# diskohedron4w_revf.net
KiCad netlist of a schematic drawn in EAGLE
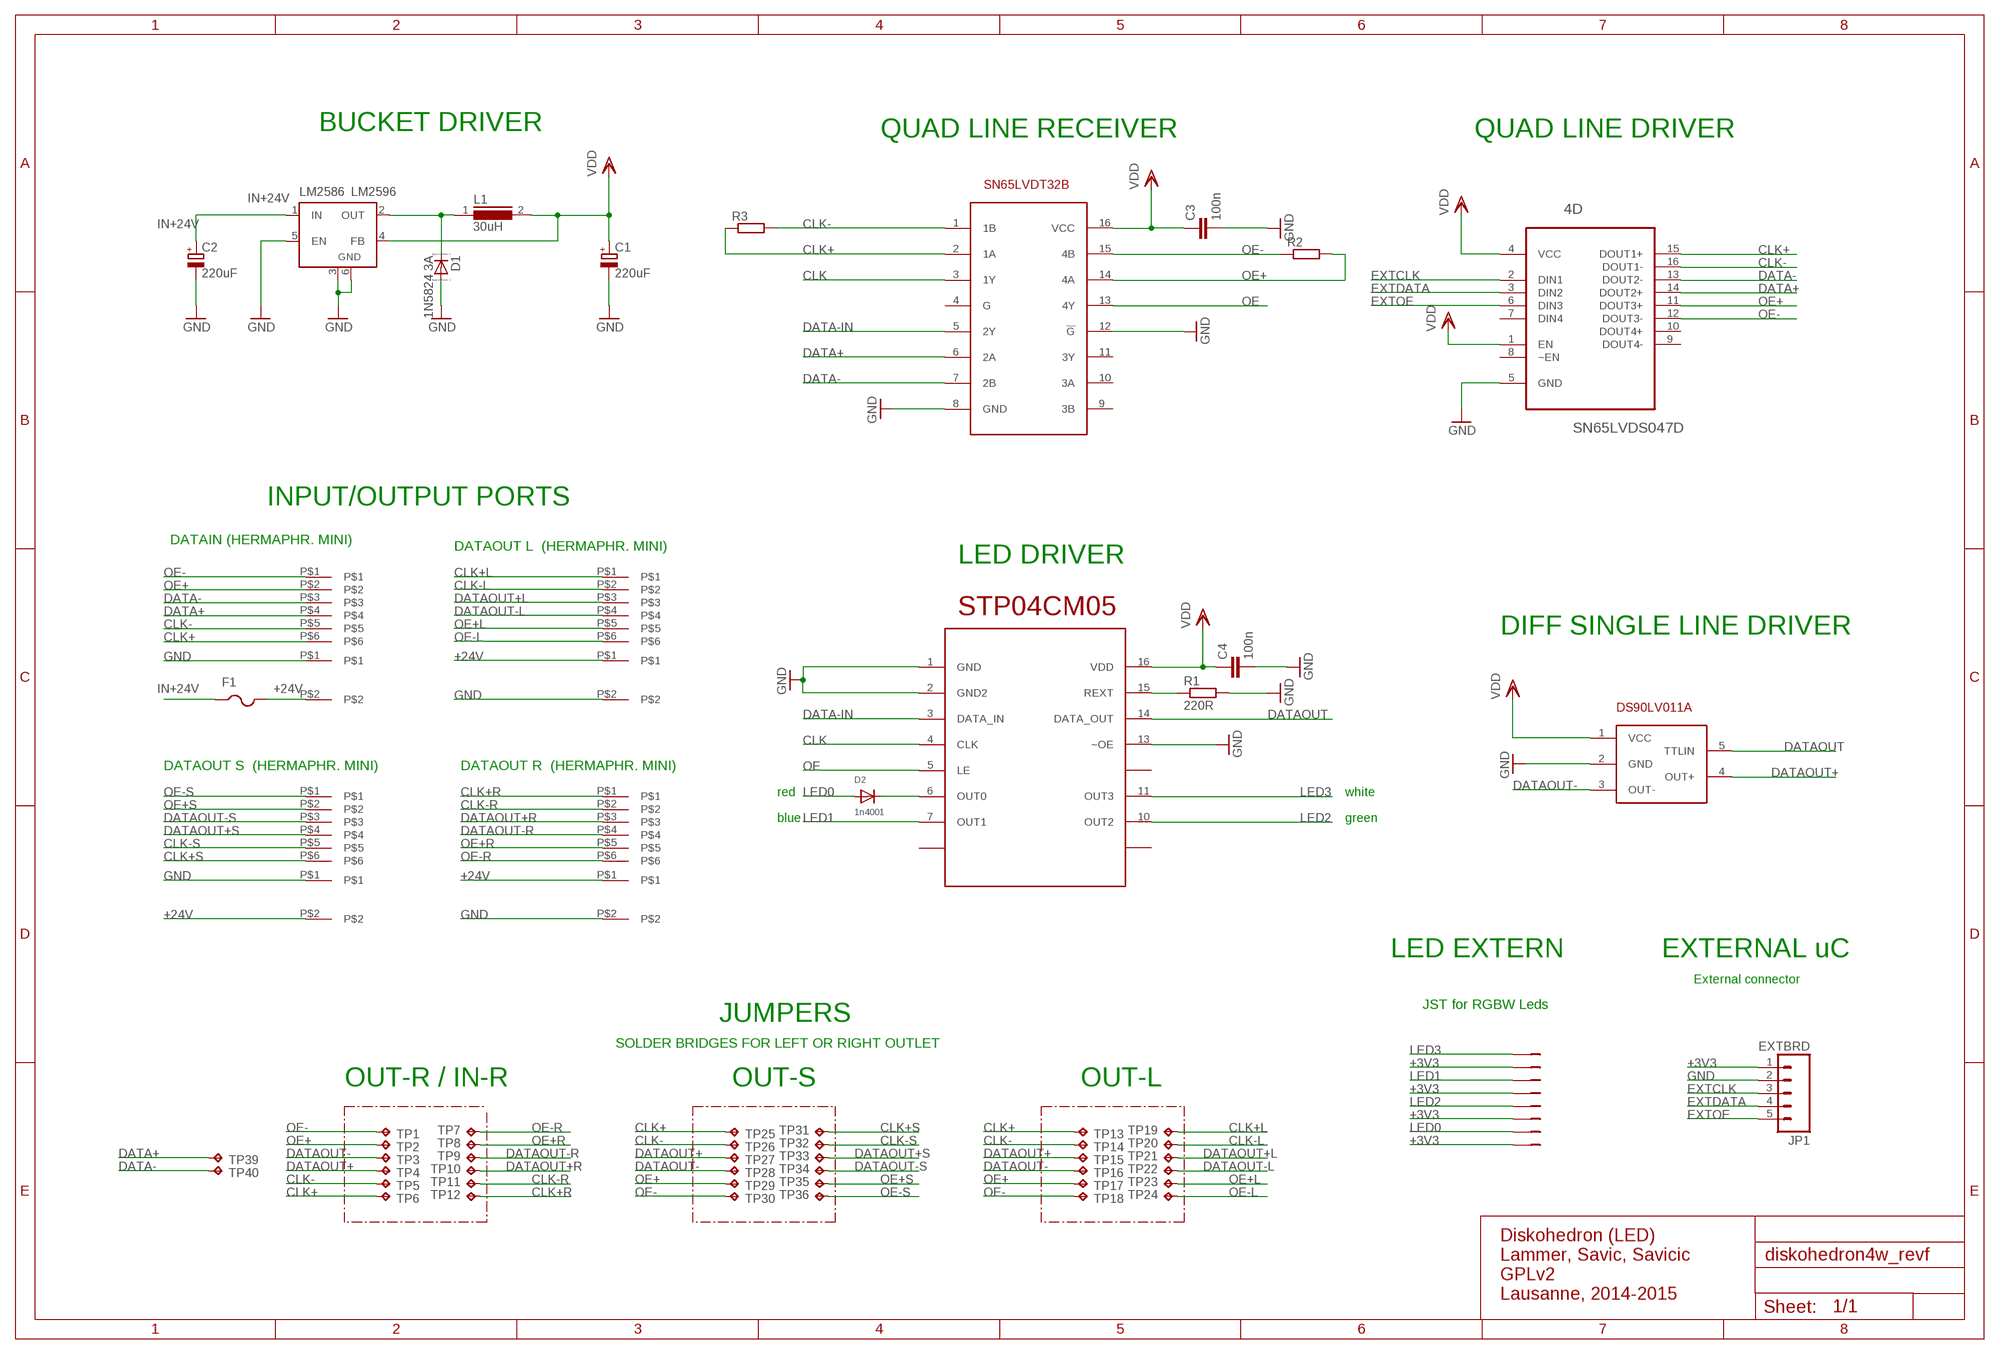
[diagram p0: schematic, sheet 1]

(export (version "E")
  (design (tool "Eeschema 10.0.6"))
  (components
    (comp (ref "1D")
      (value "DS90LV011A")
      (footprint "eagle-import:SOT23-5")
      (libsource (lib "eagle-import") (part "DS90LV011A"))
    )
    (comp (ref "4D")
      (value "SN65LVDS047D")
      (footprint "eagle-import:SOIC127P600X175-16N")
      (libsource (lib "eagle-import") (part "SN65LVDS047D"))
    )
    (comp (ref "4R")
      (value "SN65LVDST32")
      (footprint "eagle-import:SOIC16")
      (libsource (lib "eagle-import") (part "SN65LVDST32"))
    )
    (comp (ref "C1")
      (value "220uF")
      (footprint "eagle-import:153CLV-1010")
      (libsource (lib "eagle-import") (part "CPOL-EU153CLV-1010"))
    )
    (comp (ref "C2")
      (value "220uF")
      (footprint "eagle-import:153CLV-1010")
      (libsource (lib "eagle-import") (part "CPOL-EU153CLV-1010"))
    )
    (comp (ref "C3")
      (value "100n")
      (footprint "eagle-import:C0805")
      (libsource (lib "eagle-import") (part "C-EUC0805"))
    )
    (comp (ref "C4")
      (value "100n")
      (footprint "eagle-import:C0805")
      (libsource (lib "eagle-import") (part "C-EUC0805"))
    )
    (comp (ref "D1")
      (value "1N5824 3A")
      (footprint "eagle-import:DIODE_SMC")
      (libsource (lib "eagle-import") (part "DIODE_E-SMC"))
    )
    (comp (ref "D2")
      (value "1n4001")
      (footprint "eagle-import:SMADIODE")
      (libsource (lib "eagle-import") (part "DIODESMA"))
    )
    (comp (ref "F1")
      (value "PTCFUSE-1812")
      (footprint "eagle-import:1812")
      (libsource (lib "eagle-import") (part "PTCFUSE-1812"))
    )
    (comp (ref "IN1")
      (value "HERMAPHRODITMINI6PIN")
      (footprint "eagle-import:HERMAPHRODITMINI6PIN")
      (libsource (lib "eagle-import") (part "HERMAPHRODITMINI6PIN"))
    )
    (comp (ref "JP1")
      (value "EXTBRD")
      (footprint "eagle-import:1X05")
      (libsource (lib "eagle-import") (part "M05PTH"))
    )
    (comp (ref "JST")
      (value "8PIN-ZH")
      (footprint "eagle-import:B8B-ZH")
      (libsource (lib "eagle-import") (part "8PIN-ZH"))
    )
    (comp (ref "L1")
      (value "30uH")
      (footprint "eagle-import:DR127")
      (libsource (lib "eagle-import") (part "DR127"))
    )
    (comp (ref "LM2586")
      (value "LM2596")
      (footprint "eagle-import:TO263-5")
      (libsource (lib "eagle-import") (part "LM2596S"))
    )
    (comp (ref "OUT-L")
      (value "HERMAPHRODITMINI6PIN")
      (footprint "eagle-import:HERMAPHRODITMINI6PIN")
      (libsource (lib "eagle-import") (part "HERMAPHRODITMINI6PIN"))
    )
    (comp (ref "OUT-R")
      (value "HERMAPHRODITMINI6PIN")
      (footprint "eagle-import:HERMAPHRODITMINI6PIN")
      (libsource (lib "eagle-import") (part "HERMAPHRODITMINI6PIN"))
    )
    (comp (ref "OUT-S")
      (value "HERMAPHRODITMINI6PIN")
      (footprint "eagle-import:HERMAPHRODITMINI6PIN")
      (libsource (lib "eagle-import") (part "HERMAPHRODITMINI6PIN"))
    )
    (comp (ref "POWERIN")
      (value "HERMAPHRODIT2PIN")
      (footprint "eagle-import:HERMAPHRODIT2PIN")
      (libsource (lib "eagle-import") (part "HERMAPHRODIT2PIN"))
    )
    (comp (ref "POWEROUT-L")
      (value "HERMAPHRODIT2PIN")
      (footprint "eagle-import:HERMAPHRODIT2PIN")
      (libsource (lib "eagle-import") (part "HERMAPHRODIT2PIN"))
    )
    (comp (ref "POWEROUT-R")
      (value "HERMAPHRODIT2PIN")
      (footprint "eagle-import:HERMAPHRODIT2PIN")
      (libsource (lib "eagle-import") (part "HERMAPHRODIT2PIN"))
    )
    (comp (ref "POWEROUT-S")
      (value "HERMAPHRODIT2PIN")
      (footprint "eagle-import:HERMAPHRODIT2PIN")
      (libsource (lib "eagle-import") (part "HERMAPHRODIT2PIN"))
    )
    (comp (ref "R1")
      (value "220R")
      (footprint "eagle-import:M0805")
      (libsource (lib "eagle-import") (part "resistor_R-EU_M0805"))
    )
    (comp (ref "R2")
      (value "R-EU_R0603")
      (footprint "eagle-import:R0603")
      (libsource (lib "eagle-import") (part "R-EU_R0603"))
    )
    (comp (ref "R3")
      (value "R-EU_R0603")
      (footprint "eagle-import:R0603")
      (libsource (lib "eagle-import") (part "R-EU_R0603"))
    )
    (comp (ref "STP04")
      (value "STP04CM05")
      (footprint "eagle-import:TSSOP16")
      (libsource (lib "eagle-import") (part "STP04CM05"))
    )
    (comp (ref "TP1")
      (value "TPTP12SQ")
      (footprint "eagle-import:TP12SQ")
      (libsource (lib "eagle-import") (part "TPTP12SQ"))
    )
    (comp (ref "TP2")
      (value "TPTP12SQ")
      (footprint "eagle-import:TP12SQ")
      (libsource (lib "eagle-import") (part "TPTP12SQ"))
    )
    (comp (ref "TP3")
      (value "TPTP09SQ")
      (footprint "eagle-import:TP09SQ")
      (libsource (lib "eagle-import") (part "TPTP09SQ"))
    )
    (comp (ref "TP4")
      (value "TPTP09SQ")
      (footprint "eagle-import:TP09SQ")
      (libsource (lib "eagle-import") (part "TPTP09SQ"))
    )
    (comp (ref "TP5")
      (value "TPTP12SQ")
      (footprint "eagle-import:TP12SQ")
      (libsource (lib "eagle-import") (part "TPTP12SQ"))
    )
    (comp (ref "TP6")
      (value "TPTP12SQ")
      (footprint "eagle-import:TP12SQ")
      (libsource (lib "eagle-import") (part "TPTP12SQ"))
    )
    (comp (ref "TP7")
      (value "TPTP12SQ")
      (footprint "eagle-import:TP12SQ")
      (libsource (lib "eagle-import") (part "TPTP12SQ"))
    )
    (comp (ref "TP8")
      (value "TPTP12SQ")
      (footprint "eagle-import:TP12SQ")
      (libsource (lib "eagle-import") (part "TPTP12SQ"))
    )
    (comp (ref "TP9")
      (value "TPTP20SQ")
      (footprint "eagle-import:TP20SQ")
      (libsource (lib "eagle-import") (part "TPTP20SQ"))
    )
    (comp (ref "TP10")
      (value "TPTP20SQ")
      (footprint "eagle-import:TP20SQ")
      (libsource (lib "eagle-import") (part "TPTP20SQ"))
    )
    (comp (ref "TP11")
      (value "TPTP12SQ")
      (footprint "eagle-import:TP12SQ")
      (libsource (lib "eagle-import") (part "TPTP12SQ"))
    )
    (comp (ref "TP12")
      (value "TPTP12SQ")
      (footprint "eagle-import:TP12SQ")
      (libsource (lib "eagle-import") (part "TPTP12SQ"))
    )
    (comp (ref "TP13")
      (value "TPTP12SQ")
      (footprint "eagle-import:TP12SQ")
      (libsource (lib "eagle-import") (part "TPTP12SQ"))
    )
    (comp (ref "TP14")
      (value "TPTP12SQ")
      (footprint "eagle-import:TP12SQ")
      (libsource (lib "eagle-import") (part "TPTP12SQ"))
    )
    (comp (ref "TP15")
      (value "TPTP12SQ")
      (footprint "eagle-import:TP12SQ")
      (libsource (lib "eagle-import") (part "TPTP12SQ"))
    )
    (comp (ref "TP16")
      (value "TPTP12SQ")
      (footprint "eagle-import:TP12SQ")
      (libsource (lib "eagle-import") (part "TPTP12SQ"))
    )
    (comp (ref "TP17")
      (value "TPTP12SQ")
      (footprint "eagle-import:TP12SQ")
      (libsource (lib "eagle-import") (part "TPTP12SQ"))
    )
    (comp (ref "TP18")
      (value "TPTP12SQ")
      (footprint "eagle-import:TP12SQ")
      (libsource (lib "eagle-import") (part "TPTP12SQ"))
    )
    (comp (ref "TP19")
      (value "TPTP12SQ")
      (footprint "eagle-import:TP12SQ")
      (libsource (lib "eagle-import") (part "TPTP12SQ"))
    )
    (comp (ref "TP20")
      (value "TPTP12SQ")
      (footprint "eagle-import:TP12SQ")
      (libsource (lib "eagle-import") (part "TPTP12SQ"))
    )
    (comp (ref "TP21")
      (value "TPTP12SQ")
      (footprint "eagle-import:TP12SQ")
      (libsource (lib "eagle-import") (part "TPTP12SQ"))
    )
    (comp (ref "TP22")
      (value "TPTP12SQ")
      (footprint "eagle-import:TP12SQ")
      (libsource (lib "eagle-import") (part "TPTP12SQ"))
    )
    (comp (ref "TP23")
      (value "TPTP12SQ")
      (footprint "eagle-import:TP12SQ")
      (libsource (lib "eagle-import") (part "TPTP12SQ"))
    )
    (comp (ref "TP24")
      (value "TPTP12SQ")
      (footprint "eagle-import:TP12SQ")
      (libsource (lib "eagle-import") (part "TPTP12SQ"))
    )
    (comp (ref "TP25")
      (value "TPTP12SQ")
      (footprint "eagle-import:TP12SQ")
      (libsource (lib "eagle-import") (part "TPTP12SQ"))
    )
    (comp (ref "TP26")
      (value "TPTP12SQ")
      (footprint "eagle-import:TP12SQ")
      (libsource (lib "eagle-import") (part "TPTP12SQ"))
    )
    (comp (ref "TP27")
      (value "TPTP12SQ")
      (footprint "eagle-import:TP12SQ")
      (libsource (lib "eagle-import") (part "TPTP12SQ"))
    )
    (comp (ref "TP28")
      (value "TPTP12SQ")
      (footprint "eagle-import:TP12SQ")
      (libsource (lib "eagle-import") (part "TPTP12SQ"))
    )
    (comp (ref "TP29")
      (value "TPTP12SQ")
      (footprint "eagle-import:TP12SQ")
      (libsource (lib "eagle-import") (part "TPTP12SQ"))
    )
    (comp (ref "TP30")
      (value "TPTP12SQ")
      (footprint "eagle-import:TP12SQ")
      (libsource (lib "eagle-import") (part "TPTP12SQ"))
    )
    (comp (ref "TP31")
      (value "TPTP12SQ")
      (footprint "eagle-import:TP12SQ")
      (libsource (lib "eagle-import") (part "TPTP12SQ"))
    )
    (comp (ref "TP32")
      (value "TPTP12SQ")
      (footprint "eagle-import:TP12SQ")
      (libsource (lib "eagle-import") (part "TPTP12SQ"))
    )
    (comp (ref "TP33")
      (value "TPTP12SQ")
      (footprint "eagle-import:TP12SQ")
      (libsource (lib "eagle-import") (part "TPTP12SQ"))
    )
    (comp (ref "TP34")
      (value "TPTP12SQ")
      (footprint "eagle-import:TP12SQ")
      (libsource (lib "eagle-import") (part "TPTP12SQ"))
    )
    (comp (ref "TP35")
      (value "TPTP12SQ")
      (footprint "eagle-import:TP12SQ")
      (libsource (lib "eagle-import") (part "TPTP12SQ"))
    )
    (comp (ref "TP36")
      (value "TPTP12SQ")
      (footprint "eagle-import:TP12SQ")
      (libsource (lib "eagle-import") (part "TPTP12SQ"))
    )
    (comp (ref "TP39")
      (value "TPTP09SQ")
      (footprint "eagle-import:TP09SQ")
      (libsource (lib "eagle-import") (part "TPTP09SQ"))
    )
    (comp (ref "TP40")
      (value "TPTP09SQ")
      (footprint "eagle-import:TP09SQ")
      (libsource (lib "eagle-import") (part "TPTP09SQ"))
    )
  )
  (nets
    (net (code "1") (name "/+24V") (class "Default")
      (node (ref "F1") (pin "2") (pinfunction "2_2") (pintype "passive"))
      (node (ref "POWERIN") (pin "P$2") (pinfunction "P$2_P$2") (pintype "bidirectional"))
      (node (ref "POWEROUT-L") (pin "P$1") (pinfunction "P$1_P$1") (pintype "bidirectional"))
      (node (ref "POWEROUT-R") (pin "P$1") (pinfunction "P$1_P$1") (pintype "bidirectional"))
      (node (ref "POWEROUT-S") (pin "P$2") (pinfunction "P$2_P$2") (pintype "bidirectional"))
    )
    (net (code "2") (name "/CLK") (class "Default")
      (node (ref "4R") (pin "3") (pinfunction "1Y_3") (pintype "bidirectional"))
      (node (ref "STP04") (pin "4") (pinfunction "CLK_4") (pintype "bidirectional"))
    )
    (net (code "3") (name "/CLK+") (class "Default")
      (node (ref "4D") (pin "15") (pinfunction "DOUT1+_15") (pintype "output"))
      (node (ref "4R") (pin "2") (pinfunction "1A_2") (pintype "bidirectional"))
      (node (ref "IN1") (pin "P$6") (pinfunction "P$6_P$6") (pintype "bidirectional"))
      (node (ref "R3") (pin "1") (pinfunction "1_1") (pintype "passive"))
      (node (ref "TP13") (pin "TP") (pinfunction "TP_TP") (pintype "input"))
      (node (ref "TP25") (pin "TP") (pinfunction "TP_TP") (pintype "input"))
      (node (ref "TP6") (pin "TP") (pinfunction "TP_TP") (pintype "input"))
    )
    (net (code "4") (name "/CLK+L") (class "Default")
      (node (ref "OUT-L") (pin "P$1") (pinfunction "P$1_P$1") (pintype "bidirectional"))
      (node (ref "TP19") (pin "TP") (pinfunction "TP_TP") (pintype "input"))
    )
    (net (code "5") (name "/CLK+R") (class "Default")
      (node (ref "OUT-R") (pin "P$1") (pinfunction "P$1_P$1") (pintype "bidirectional"))
      (node (ref "TP12") (pin "TP") (pinfunction "TP_TP") (pintype "input"))
    )
    (net (code "6") (name "/CLK+S") (class "Default")
      (node (ref "OUT-S") (pin "P$6") (pinfunction "P$6_P$6") (pintype "bidirectional"))
      (node (ref "TP31") (pin "TP") (pinfunction "TP_TP") (pintype "input"))
    )
    (net (code "7") (name "/CLK-") (class "Default")
      (node (ref "4D") (pin "16") (pinfunction "DOUT1-_16") (pintype "output"))
      (node (ref "4R") (pin "1") (pinfunction "1B_1") (pintype "bidirectional"))
      (node (ref "IN1") (pin "P$5") (pinfunction "P$5_P$5") (pintype "bidirectional"))
      (node (ref "R3") (pin "2") (pinfunction "2_2") (pintype "passive"))
      (node (ref "TP14") (pin "TP") (pinfunction "TP_TP") (pintype "input"))
      (node (ref "TP26") (pin "TP") (pinfunction "TP_TP") (pintype "input"))
      (node (ref "TP5") (pin "TP") (pinfunction "TP_TP") (pintype "input"))
    )
    (net (code "8") (name "/CLK-L") (class "Default")
      (node (ref "OUT-L") (pin "P$2") (pinfunction "P$2_P$2") (pintype "bidirectional"))
      (node (ref "TP20") (pin "TP") (pinfunction "TP_TP") (pintype "input"))
    )
    (net (code "9") (name "/CLK-R") (class "Default")
      (node (ref "OUT-R") (pin "P$2") (pinfunction "P$2_P$2") (pintype "bidirectional"))
      (node (ref "TP11") (pin "TP") (pinfunction "TP_TP") (pintype "input"))
    )
    (net (code "10") (name "/CLK-S") (class "Default")
      (node (ref "OUT-S") (pin "P$5") (pinfunction "P$5_P$5") (pintype "bidirectional"))
      (node (ref "TP32") (pin "TP") (pinfunction "TP_TP") (pintype "input"))
    )
    (net (code "11") (name "/DATA+") (class "Default")
      (node (ref "4D") (pin "14") (pinfunction "DOUT2+_14") (pintype "output"))
      (node (ref "4R") (pin "6") (pinfunction "2A_6") (pintype "bidirectional"))
      (node (ref "IN1") (pin "P$4") (pinfunction "P$4_P$4") (pintype "bidirectional"))
      (node (ref "TP39") (pin "TP") (pinfunction "TP_TP") (pintype "input"))
    )
    (net (code "12") (name "/DATA-") (class "Default")
      (node (ref "4D") (pin "13") (pinfunction "DOUT2-_13") (pintype "output"))
      (node (ref "4R") (pin "7") (pinfunction "2B_7") (pintype "bidirectional"))
      (node (ref "IN1") (pin "P$3") (pinfunction "P$3_P$3") (pintype "bidirectional"))
      (node (ref "TP40") (pin "TP") (pinfunction "TP_TP") (pintype "input"))
    )
    (net (code "13") (name "/DATA-IN") (class "Default")
      (node (ref "4R") (pin "5") (pinfunction "2Y_5") (pintype "bidirectional"))
      (node (ref "STP04") (pin "3") (pinfunction "DATA_IN_3") (pintype "bidirectional"))
    )
    (net (code "14") (name "/DATAOUT") (class "Default")
      (node (ref "1D") (pin "5") (pinfunction "TTLIN_5") (pintype "bidirectional"))
      (node (ref "STP04") (pin "14") (pinfunction "DATA_OUT_14") (pintype "bidirectional"))
    )
    (net (code "15") (name "/DATAOUT+") (class "Default")
      (node (ref "1D") (pin "4") (pinfunction "OUT+_4") (pintype "bidirectional"))
      (node (ref "TP15") (pin "TP") (pinfunction "TP_TP") (pintype "input"))
      (node (ref "TP27") (pin "TP") (pinfunction "TP_TP") (pintype "input"))
      (node (ref "TP4") (pin "TP") (pinfunction "TP_TP") (pintype "input"))
    )
    (net (code "16") (name "/DATAOUT+L") (class "Default")
      (node (ref "OUT-L") (pin "P$3") (pinfunction "P$3_P$3") (pintype "bidirectional"))
      (node (ref "TP21") (pin "TP") (pinfunction "TP_TP") (pintype "input"))
    )
    (net (code "17") (name "/DATAOUT+R") (class "Default")
      (node (ref "OUT-R") (pin "P$3") (pinfunction "P$3_P$3") (pintype "bidirectional"))
      (node (ref "TP10") (pin "TP") (pinfunction "TP_TP") (pintype "input"))
    )
    (net (code "18") (name "/DATAOUT+S") (class "Default")
      (node (ref "OUT-S") (pin "P$4") (pinfunction "P$4_P$4") (pintype "bidirectional"))
      (node (ref "TP33") (pin "TP") (pinfunction "TP_TP") (pintype "input"))
    )
    (net (code "19") (name "/DATAOUT-") (class "Default")
      (node (ref "1D") (pin "3") (pinfunction "OUT-_3") (pintype "bidirectional"))
      (node (ref "TP16") (pin "TP") (pinfunction "TP_TP") (pintype "input"))
      (node (ref "TP28") (pin "TP") (pinfunction "TP_TP") (pintype "input"))
      (node (ref "TP3") (pin "TP") (pinfunction "TP_TP") (pintype "input"))
    )
    (net (code "20") (name "/DATAOUT-L") (class "Default")
      (node (ref "OUT-L") (pin "P$4") (pinfunction "P$4_P$4") (pintype "bidirectional"))
      (node (ref "TP22") (pin "TP") (pinfunction "TP_TP") (pintype "input"))
    )
    (net (code "21") (name "/DATAOUT-R") (class "Default")
      (node (ref "OUT-R") (pin "P$4") (pinfunction "P$4_P$4") (pintype "bidirectional"))
      (node (ref "TP9") (pin "TP") (pinfunction "TP_TP") (pintype "input"))
    )
    (net (code "22") (name "/DATAOUT-S") (class "Default")
      (node (ref "OUT-S") (pin "P$3") (pinfunction "P$3_P$3") (pintype "bidirectional"))
      (node (ref "TP34") (pin "TP") (pinfunction "TP_TP") (pintype "input"))
    )
    (net (code "23") (name "/EXTCLK") (class "Default")
      (node (ref "4D") (pin "2") (pinfunction "DIN1_2") (pintype "input"))
      (node (ref "JP1") (pin "3") (pinfunction "3_3") (pintype "passive"))
    )
    (net (code "24") (name "/EXTDATA") (class "Default")
      (node (ref "4D") (pin "3") (pinfunction "DIN2_3") (pintype "input"))
      (node (ref "JP1") (pin "4") (pinfunction "4_4") (pintype "passive"))
    )
    (net (code "25") (name "/EXTOE") (class "Default")
      (node (ref "4D") (pin "6") (pinfunction "DIN3_6") (pintype "input"))
      (node (ref "JP1") (pin "5") (pinfunction "5_5") (pintype "passive"))
    )
    (net (code "26") (name "/IN+24V") (class "Default")
      (node (ref "C2") (pin "+") (pinfunction "+_+") (pintype "passive"))
      (node (ref "F1") (pin "1") (pinfunction "1_1") (pintype "passive"))
      (node (ref "LM2586") (pin "1") (pinfunction "IN_1") (pintype "input"))
    )
    (net (code "27") (name "/LED0") (class "Default")
      (node (ref "D2") (pin "A") (pinfunction "A_A") (pintype "passive"))
      (node (ref "JST") (pin "7") (pinfunction "1_7") (pintype "passive"))
    )
    (net (code "28") (name "/LED1") (class "Default")
      (node (ref "JST") (pin "3") (pinfunction "1_3") (pintype "passive"))
      (node (ref "STP04") (pin "7") (pinfunction "OUT1_7") (pintype "bidirectional"))
    )
    (net (code "29") (name "/LED2") (class "Default")
      (node (ref "JST") (pin "5") (pinfunction "1_5") (pintype "passive"))
      (node (ref "STP04") (pin "10") (pinfunction "OUT2_10") (pintype "bidirectional"))
    )
    (net (code "30") (name "/LED3") (class "Default")
      (node (ref "JST") (pin "1") (pinfunction "1_1") (pintype "passive"))
      (node (ref "STP04") (pin "11") (pinfunction "OUT3_11") (pintype "bidirectional"))
    )
    (net (code "31") (name "/OE") (class "Default")
      (node (ref "4R") (pin "13") (pinfunction "4Y_13") (pintype "bidirectional"))
      (node (ref "STP04") (pin "5") (pinfunction "LE_5") (pintype "bidirectional"))
    )
    (net (code "32") (name "/OE+") (class "Default")
      (node (ref "4D") (pin "11") (pinfunction "DOUT3+_11") (pintype "output"))
      (node (ref "4R") (pin "14") (pinfunction "4A_14") (pintype "bidirectional"))
      (node (ref "IN1") (pin "P$2") (pinfunction "P$2_P$2") (pintype "bidirectional"))
      (node (ref "R2") (pin "2") (pinfunction "2_2") (pintype "passive"))
      (node (ref "TP17") (pin "TP") (pinfunction "TP_TP") (pintype "input"))
      (node (ref "TP2") (pin "TP") (pinfunction "TP_TP") (pintype "input"))
      (node (ref "TP29") (pin "TP") (pinfunction "TP_TP") (pintype "input"))
    )
    (net (code "33") (name "/OE+L") (class "Default")
      (node (ref "OUT-L") (pin "P$5") (pinfunction "P$5_P$5") (pintype "bidirectional"))
      (node (ref "TP23") (pin "TP") (pinfunction "TP_TP") (pintype "input"))
    )
    (net (code "34") (name "/OE+R") (class "Default")
      (node (ref "OUT-R") (pin "P$5") (pinfunction "P$5_P$5") (pintype "bidirectional"))
      (node (ref "TP8") (pin "TP") (pinfunction "TP_TP") (pintype "input"))
    )
    (net (code "35") (name "/OE+S") (class "Default")
      (node (ref "OUT-S") (pin "P$2") (pinfunction "P$2_P$2") (pintype "bidirectional"))
      (node (ref "TP35") (pin "TP") (pinfunction "TP_TP") (pintype "input"))
    )
    (net (code "36") (name "/OE-") (class "Default")
      (node (ref "4D") (pin "12") (pinfunction "DOUT3-_12") (pintype "output"))
      (node (ref "4R") (pin "15") (pinfunction "4B_15") (pintype "bidirectional"))
      (node (ref "IN1") (pin "P$1") (pinfunction "P$1_P$1") (pintype "bidirectional"))
      (node (ref "R2") (pin "1") (pinfunction "1_1") (pintype "passive"))
      (node (ref "TP1") (pin "TP") (pinfunction "TP_TP") (pintype "input"))
      (node (ref "TP18") (pin "TP") (pinfunction "TP_TP") (pintype "input"))
      (node (ref "TP30") (pin "TP") (pinfunction "TP_TP") (pintype "input"))
    )
    (net (code "37") (name "/OE-L") (class "Default")
      (node (ref "OUT-L") (pin "P$6") (pinfunction "P$6_P$6") (pintype "bidirectional"))
      (node (ref "TP24") (pin "TP") (pinfunction "TP_TP") (pintype "input"))
    )
    (net (code "38") (name "/OE-R") (class "Default")
      (node (ref "OUT-R") (pin "P$6") (pinfunction "P$6_P$6") (pintype "bidirectional"))
      (node (ref "TP7") (pin "TP") (pinfunction "TP_TP") (pintype "input"))
    )
    (net (code "39") (name "/OE-S") (class "Default")
      (node (ref "OUT-S") (pin "P$1") (pinfunction "P$1_P$1") (pintype "bidirectional"))
      (node (ref "TP36") (pin "TP") (pinfunction "TP_TP") (pintype "input"))
    )
    (net (code "40") (name "GND") (class "Default")
      (node (ref "1D") (pin "2") (pinfunction "GND_2") (pintype "bidirectional"))
      (node (ref "4D") (pin "5") (pinfunction "GND_5") (pintype "passive"))
      (node (ref "4R") (pin "12") (pinfunction "~{G}_12") (pintype "bidirectional"))
      (node (ref "4R") (pin "8") (pinfunction "GND_8") (pintype "bidirectional"))
      (node (ref "C1") (pin "-") (pinfunction "-_-") (pintype "passive"))
      (node (ref "C2") (pin "-") (pinfunction "-_-") (pintype "passive"))
      (node (ref "C3") (pin "2") (pinfunction "2_2") (pintype "passive"))
      (node (ref "C4") (pin "2") (pinfunction "2_2") (pintype "passive"))
      (node (ref "D1") (pin "A") (pinfunction "C_A") (pintype "passive"))
      (node (ref "JP1") (pin "2") (pinfunction "2_2") (pintype "passive"))
      (node (ref "LM2586") (pin "3") (pinfunction "GND_3") (pintype "power_in"))
      (node (ref "LM2586") (pin "5") (pinfunction "EN_5") (pintype "input"))
      (node (ref "LM2586") (pin "6") (pinfunction "GND_6") (pintype "power_in"))
      (node (ref "POWERIN") (pin "P$1") (pinfunction "P$1_P$1") (pintype "bidirectional"))
      (node (ref "POWEROUT-L") (pin "P$2") (pinfunction "P$2_P$2") (pintype "bidirectional"))
      (node (ref "POWEROUT-R") (pin "P$2") (pinfunction "P$2_P$2") (pintype "bidirectional"))
      (node (ref "POWEROUT-S") (pin "P$1") (pinfunction "P$1_P$1") (pintype "bidirectional"))
      (node (ref "R1") (pin "2") (pinfunction "2_2") (pintype "passive"))
      (node (ref "STP04") (pin "1") (pinfunction "GND_1") (pintype "bidirectional"))
      (node (ref "STP04") (pin "13") (pinfunction "~{OE}_13") (pintype "bidirectional"))
      (node (ref "STP04") (pin "2") (pinfunction "GND2_2") (pintype "bidirectional"))
    )
    (net (code "41") (name "Net-(D1-A)") (class "Default")
      (node (ref "D1") (pin "C") (pinfunction "A_C") (pintype "passive"))
      (node (ref "L1") (pin "1") (pinfunction "1_1") (pintype "passive"))
      (node (ref "LM2586") (pin "2") (pinfunction "OUT_2") (pintype "output"))
    )
    (net (code "42") (name "Net-(STP04-OUT0)") (class "Default")
      (node (ref "D2") (pin "C") (pinfunction "C_C") (pintype "passive"))
      (node (ref "STP04") (pin "6") (pinfunction "OUT0_6") (pintype "bidirectional"))
    )
    (net (code "43") (name "Net-(STP04-REXT)") (class "Default")
      (node (ref "R1") (pin "1") (pinfunction "1_1") (pintype "passive"))
      (node (ref "STP04") (pin "15") (pinfunction "REXT_15") (pintype "bidirectional"))
    )
    (net (code "44") (name "VDD") (class "Default")
      (node (ref "1D") (pin "1") (pinfunction "VCC_1") (pintype "bidirectional"))
      (node (ref "4D") (pin "1") (pinfunction "EN_1") (pintype "input"))
      (node (ref "4D") (pin "4") (pinfunction "VCC_4") (pintype "power_in"))
      (node (ref "4R") (pin "16") (pinfunction "VCC_16") (pintype "bidirectional"))
      (node (ref "C1") (pin "+") (pinfunction "+_+") (pintype "passive"))
      (node (ref "C3") (pin "1") (pinfunction "1_1") (pintype "passive"))
      (node (ref "C4") (pin "1") (pinfunction "1_1") (pintype "passive"))
      (node (ref "JP1") (pin "1") (pinfunction "1_1") (pintype "passive"))
      (node (ref "JST") (pin "2") (pinfunction "1_2") (pintype "passive"))
      (node (ref "JST") (pin "4") (pinfunction "1_4") (pintype "passive"))
      (node (ref "JST") (pin "6") (pinfunction "1_6") (pintype "passive"))
      (node (ref "JST") (pin "8") (pinfunction "1_8") (pintype "passive"))
      (node (ref "L1") (pin "2") (pinfunction "2_2") (pintype "passive"))
      (node (ref "LM2586") (pin "4") (pinfunction "FB_4") (pintype "input"))
      (node (ref "STP04") (pin "16") (pinfunction "VDD_16") (pintype "bidirectional"))
    )
    (net (code "45") (name "unconnected-(4D-DIN4-Pad7)") (class "Default")
      (node (ref "4D") (pin "7") (pinfunction "DIN4_7") (pintype "input"))
    )
    (net (code "46") (name "unconnected-(4D-DOUT4+-Pad10)") (class "Default")
      (node (ref "4D") (pin "10") (pinfunction "DOUT4+_10") (pintype "output"))
    )
    (net (code "47") (name "unconnected-(4D-DOUT4--Pad9)") (class "Default")
      (node (ref "4D") (pin "9") (pinfunction "DOUT4-_9") (pintype "output"))
    )
    (net (code "48") (name "unconnected-(4D-~{EN}-Pad8)") (class "Default")
      (node (ref "4D") (pin "8") (pinfunction "~{EN}_8") (pintype "input"))
    )
    (net (code "49") (name "unconnected-(4R-3A-Pad10)") (class "Default")
      (node (ref "4R") (pin "10") (pinfunction "3A_10") (pintype "bidirectional"))
    )
    (net (code "50") (name "unconnected-(4R-3B-Pad9)") (class "Default")
      (node (ref "4R") (pin "9") (pinfunction "3B_9") (pintype "bidirectional"))
    )
    (net (code "51") (name "unconnected-(4R-3Y-Pad11)") (class "Default")
      (node (ref "4R") (pin "11") (pinfunction "3Y_11") (pintype "bidirectional"))
    )
    (net (code "52") (name "unconnected-(4R-G-Pad4)") (class "Default")
      (node (ref "4R") (pin "4") (pinfunction "G_4") (pintype "bidirectional"))
    )
    (net (code "53") (name "unconnected-(STP04-N.C1-Pad8)") (class "Default")
      (node (ref "STP04") (pin "8") (pinfunction "N.C1_8") (pintype "bidirectional"))
    )
    (net (code "54") (name "unconnected-(STP04-NC-Pad9)") (class "Default")
      (node (ref "STP04") (pin "9") (pinfunction "NC_9") (pintype "bidirectional"))
    )
    (net (code "55") (name "unconnected-(STP04-NC3-Pad12)") (class "Default")
      (node (ref "STP04") (pin "12") (pinfunction "NC3_12") (pintype "bidirectional"))
    )
  )
)
